# 1-Top.net
KiCad netlist of a schematic drawn in Altium Designer
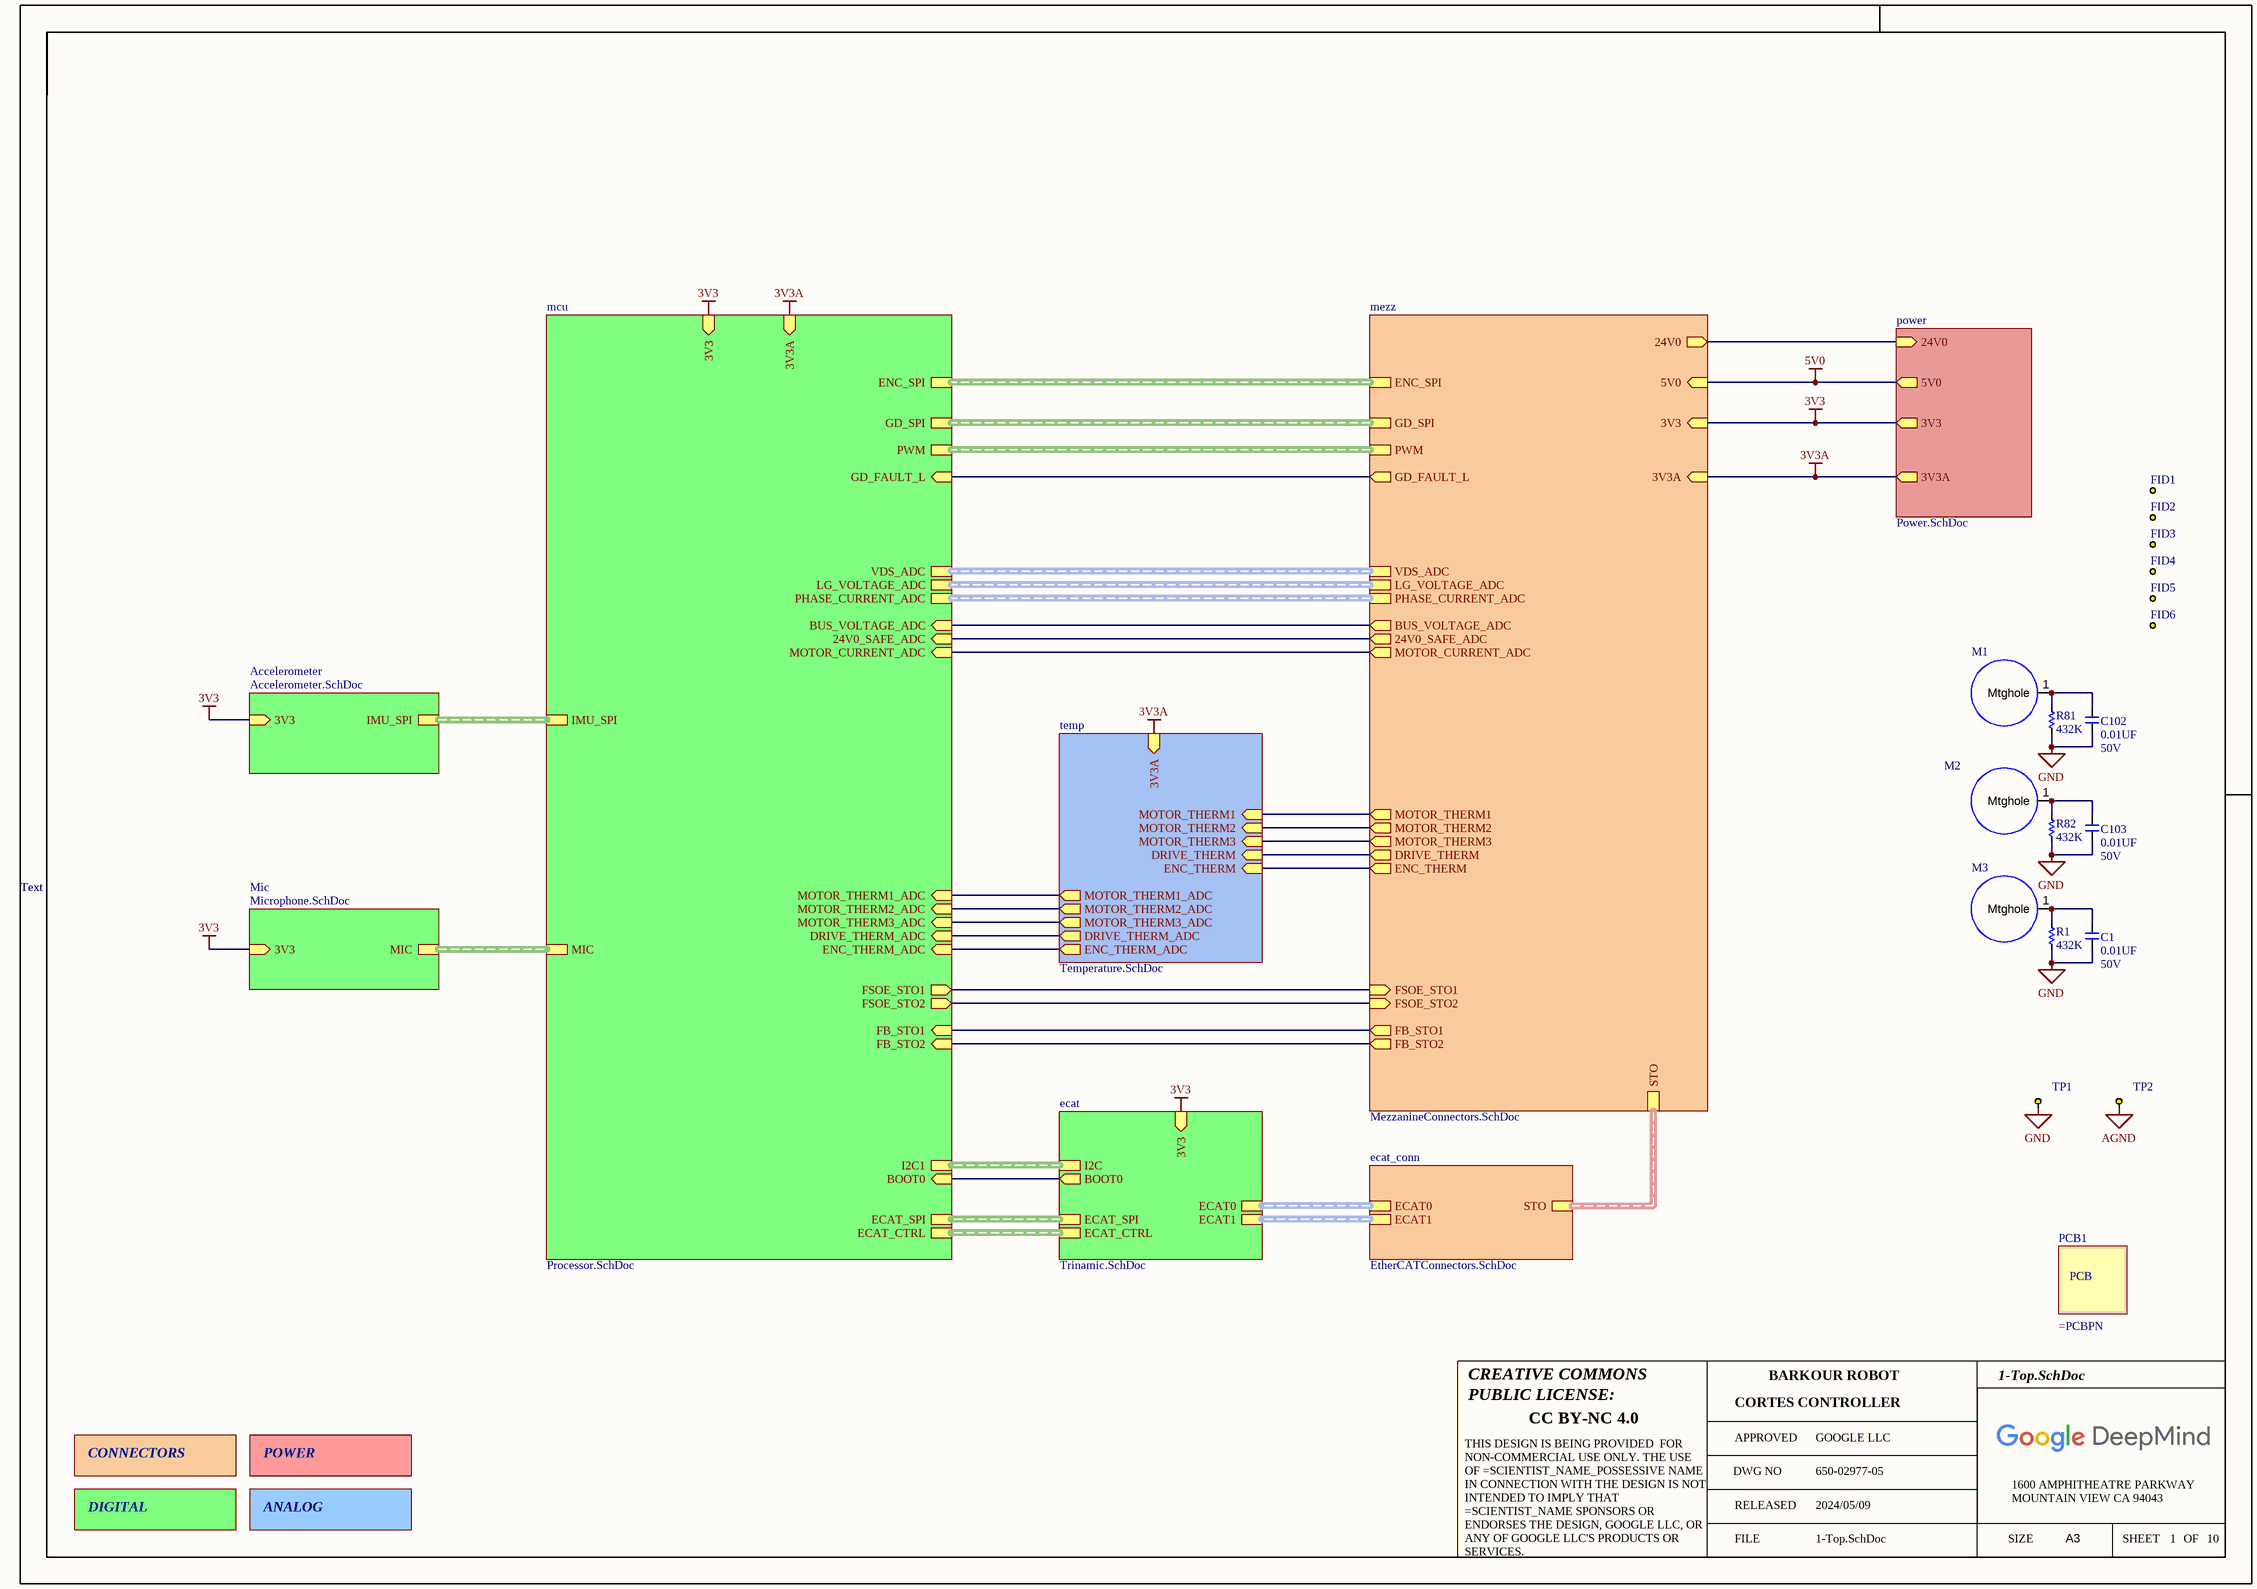
[diagram p0: 1-Top.SchDoc]

(export (version "E")
  (design (tool "Eeschema 10.0.6"))
  (components
    (comp (ref "C1")
      (value "0.01UF")
      (footprint "C0402")
      (description "CAP, CER, X7R, 0.01uF, 50V, 20%, 0402, 0.56mm T")
      (fields (field (name "MFG") "KEMET") (field (name "VOLTAGE") "50V") (field (name "TOLERANCE") "20%"))
      (libsource (lib "AltiumReleaseLibDB") (part "__Template_Cap"))
    )
    (comp (ref "C102")
      (value "0.01UF")
      (footprint "C0402")
      (description "CAP, CER, X7R, 0.01uF, 50V, 20%, 0402, 0.56mm T")
      (fields (field (name "MFG") "KEMET") (field (name "VOLTAGE") "50V") (field (name "TOLERANCE") "20%"))
      (libsource (lib "AltiumReleaseLibDB") (part "__Template_Cap"))
    )
    (comp (ref "C103")
      (value "0.01UF")
      (footprint "C0402")
      (description "CAP, CER, X7R, 0.01uF, 50V, 20%, 0402, 0.56mm T")
      (fields (field (name "MFG") "KEMET") (field (name "VOLTAGE") "50V") (field (name "TOLERANCE") "20%"))
      (libsource (lib "AltiumReleaseLibDB") (part "__Template_Cap"))
    )
    (comp (ref "FID1")
      (value "FIDUCIAL")
      (footprint "FIDUCIAL_1MM")
      (description "FIDUCIAL 1MM COPPER CIRCLE 3MM MASK PULLBACK")
      (fields (field (name "MFG") "_PCB Feature"))
      (libsource (lib "AltiumReleaseLibDB") (part "FIDUCIAL"))
    )
    (comp (ref "FID2")
      (value "FIDUCIAL")
      (footprint "FIDUCIAL_1MM")
      (description "FIDUCIAL 1MM COPPER CIRCLE 3MM MASK PULLBACK")
      (fields (field (name "MFG") "_PCB Feature"))
      (libsource (lib "AltiumReleaseLibDB") (part "FIDUCIAL"))
    )
    (comp (ref "FID3")
      (value "FIDUCIAL")
      (footprint "FIDUCIAL_1MM")
      (description "FIDUCIAL 1MM COPPER CIRCLE 3MM MASK PULLBACK")
      (fields (field (name "MFG") "_PCB Feature"))
      (libsource (lib "AltiumReleaseLibDB") (part "FIDUCIAL"))
    )
    (comp (ref "FID4")
      (value "FIDUCIAL")
      (footprint "FIDUCIAL_1MM")
      (description "FIDUCIAL 1MM COPPER CIRCLE 3MM MASK PULLBACK")
      (fields (field (name "MFG") "_PCB Feature"))
      (libsource (lib "AltiumReleaseLibDB") (part "FIDUCIAL"))
    )
    (comp (ref "FID5")
      (value "FIDUCIAL")
      (footprint "FIDUCIAL_1MM")
      (description "FIDUCIAL 1MM COPPER CIRCLE 3MM MASK PULLBACK")
      (fields (field (name "MFG") "_PCB Feature"))
      (libsource (lib "AltiumReleaseLibDB") (part "FIDUCIAL"))
    )
    (comp (ref "FID6")
      (value "FIDUCIAL")
      (footprint "FIDUCIAL_1MM")
      (description "FIDUCIAL 1MM COPPER CIRCLE 3MM MASK PULLBACK")
      (fields (field (name "MFG") "_PCB Feature"))
      (libsource (lib "AltiumReleaseLibDB") (part "FIDUCIAL"))
    )
    (comp (ref "M1")
      (value "3.7mm hole 5mm pad")
      (footprint "3.7hole5pad")
      (libsource (lib "MiscSch1") (part "MtgHole"))
    )
    (comp (ref "M2")
      (value "3.7mm hole 5mm pad")
      (footprint "3.7hole5pad")
      (libsource (lib "MiscSch1") (part "MtgHole"))
    )
    (comp (ref "M3")
      (value "3.7mm hole 5mm pad")
      (footprint "3.7hole5pad")
      (libsource (lib "MiscSch1") (part "MtgHole"))
    )
    (comp (ref "PCB1")
      (value "651-PCB")
      (description "PCB")
      (libsource (lib "AltiumReleaseLibDB") (part "Label"))
    )
    (comp (ref "R1")
      (value "432K")
      (footprint "R0805")
      (description "Resistor, 432K Ohms, 0805, 0.125W, ±1%")
      (fields (field (name "MFG") "YAGEO") (field (name "POWER") "1/8W"))
      (libsource (lib "AltiumReleaseLibDB") (part "__Template_Resistor"))
    )
    (comp (ref "R81")
      (value "432K")
      (footprint "R0805")
      (description "Resistor, 432K Ohms, 0805, 0.125W, ±1%")
      (fields (field (name "MFG") "YAGEO") (field (name "POWER") "1/8W"))
      (libsource (lib "AltiumReleaseLibDB") (part "__Template_Resistor"))
    )
    (comp (ref "R82")
      (value "432K")
      (footprint "R0805")
      (description "Resistor, 432K Ohms, 0805, 0.125W, ±1%")
      (fields (field (name "MFG") "YAGEO") (field (name "POWER") "1/8W"))
      (libsource (lib "AltiumReleaseLibDB") (part "__Template_Resistor"))
    )
    (comp (ref "TP1")
      (value "TEST_KEYSTONE5001")
      (footprint "TP_KEYSTONE_5001")
      (description "PC TEST POINT TH RING")
      (fields
        (field (name "MANUFACTURER") "Keystone Electronics")
        (field (name "MANUFACTURER PART NUMBER") "5001")
      )
      (libsource (lib "miscellaneous") (part "TEST_KEYSTONE5001"))
    )
    (comp (ref "TP2")
      (value "TEST_KEYSTONE5001")
      (footprint "TP_KEYSTONE_5001")
      (description "PC TEST POINT TH RING")
      (fields
        (field (name "MANUFACTURER") "Keystone Electronics")
        (field (name "MANUFACTURER PART NUMBER") "5001")
      )
      (libsource (lib "miscellaneous") (part "TEST_KEYSTONE5001"))
    )
  )
  (nets
    (net (code "38") (name "AGND") (class "Default") (node (ref "TP2") (pin "1") (pintype "passive")))
    (net (code "39") (name "GND") (class "Default")
      (node (ref "C1") (pin "2") (pintype "passive"))
      (node (ref "C102") (pin "2") (pintype "passive"))
      (node (ref "C103") (pin "2") (pintype "passive"))
      (node (ref "R1") (pin "1") (pintype "passive"))
      (node (ref "R81") (pin "1") (pintype "passive"))
      (node (ref "R82") (pin "1") (pintype "passive"))
      (node (ref "TP1") (pin "1") (pintype "passive"))
    )
    (net (code "40") (name "Net-(M1-Mtghole)") (class "Default")
      (node (ref "C102") (pin "1") (pintype "passive"))
      (node (ref "M1") (pin "1") (pinfunction "Mtghole_1") (pintype "passive"))
      (node (ref "R81") (pin "2") (pintype "passive"))
    )
    (net (code "41") (name "Net-(M2-Mtghole)") (class "Default")
      (node (ref "C103") (pin "1") (pintype "passive"))
      (node (ref "M2") (pin "1") (pinfunction "Mtghole_1") (pintype "passive"))
      (node (ref "R82") (pin "2") (pintype "passive"))
    )
    (net (code "42") (name "Net-(M3-Mtghole)") (class "Default")
      (node (ref "C1") (pin "1") (pintype "passive"))
      (node (ref "M3") (pin "1") (pinfunction "Mtghole_1") (pintype "passive"))
      (node (ref "R1") (pin "2") (pintype "passive"))
    )
  )
)
